# DB10012_ControlEtherCAT.net
KiCad netlist of a schematic drawn in Altium Designer
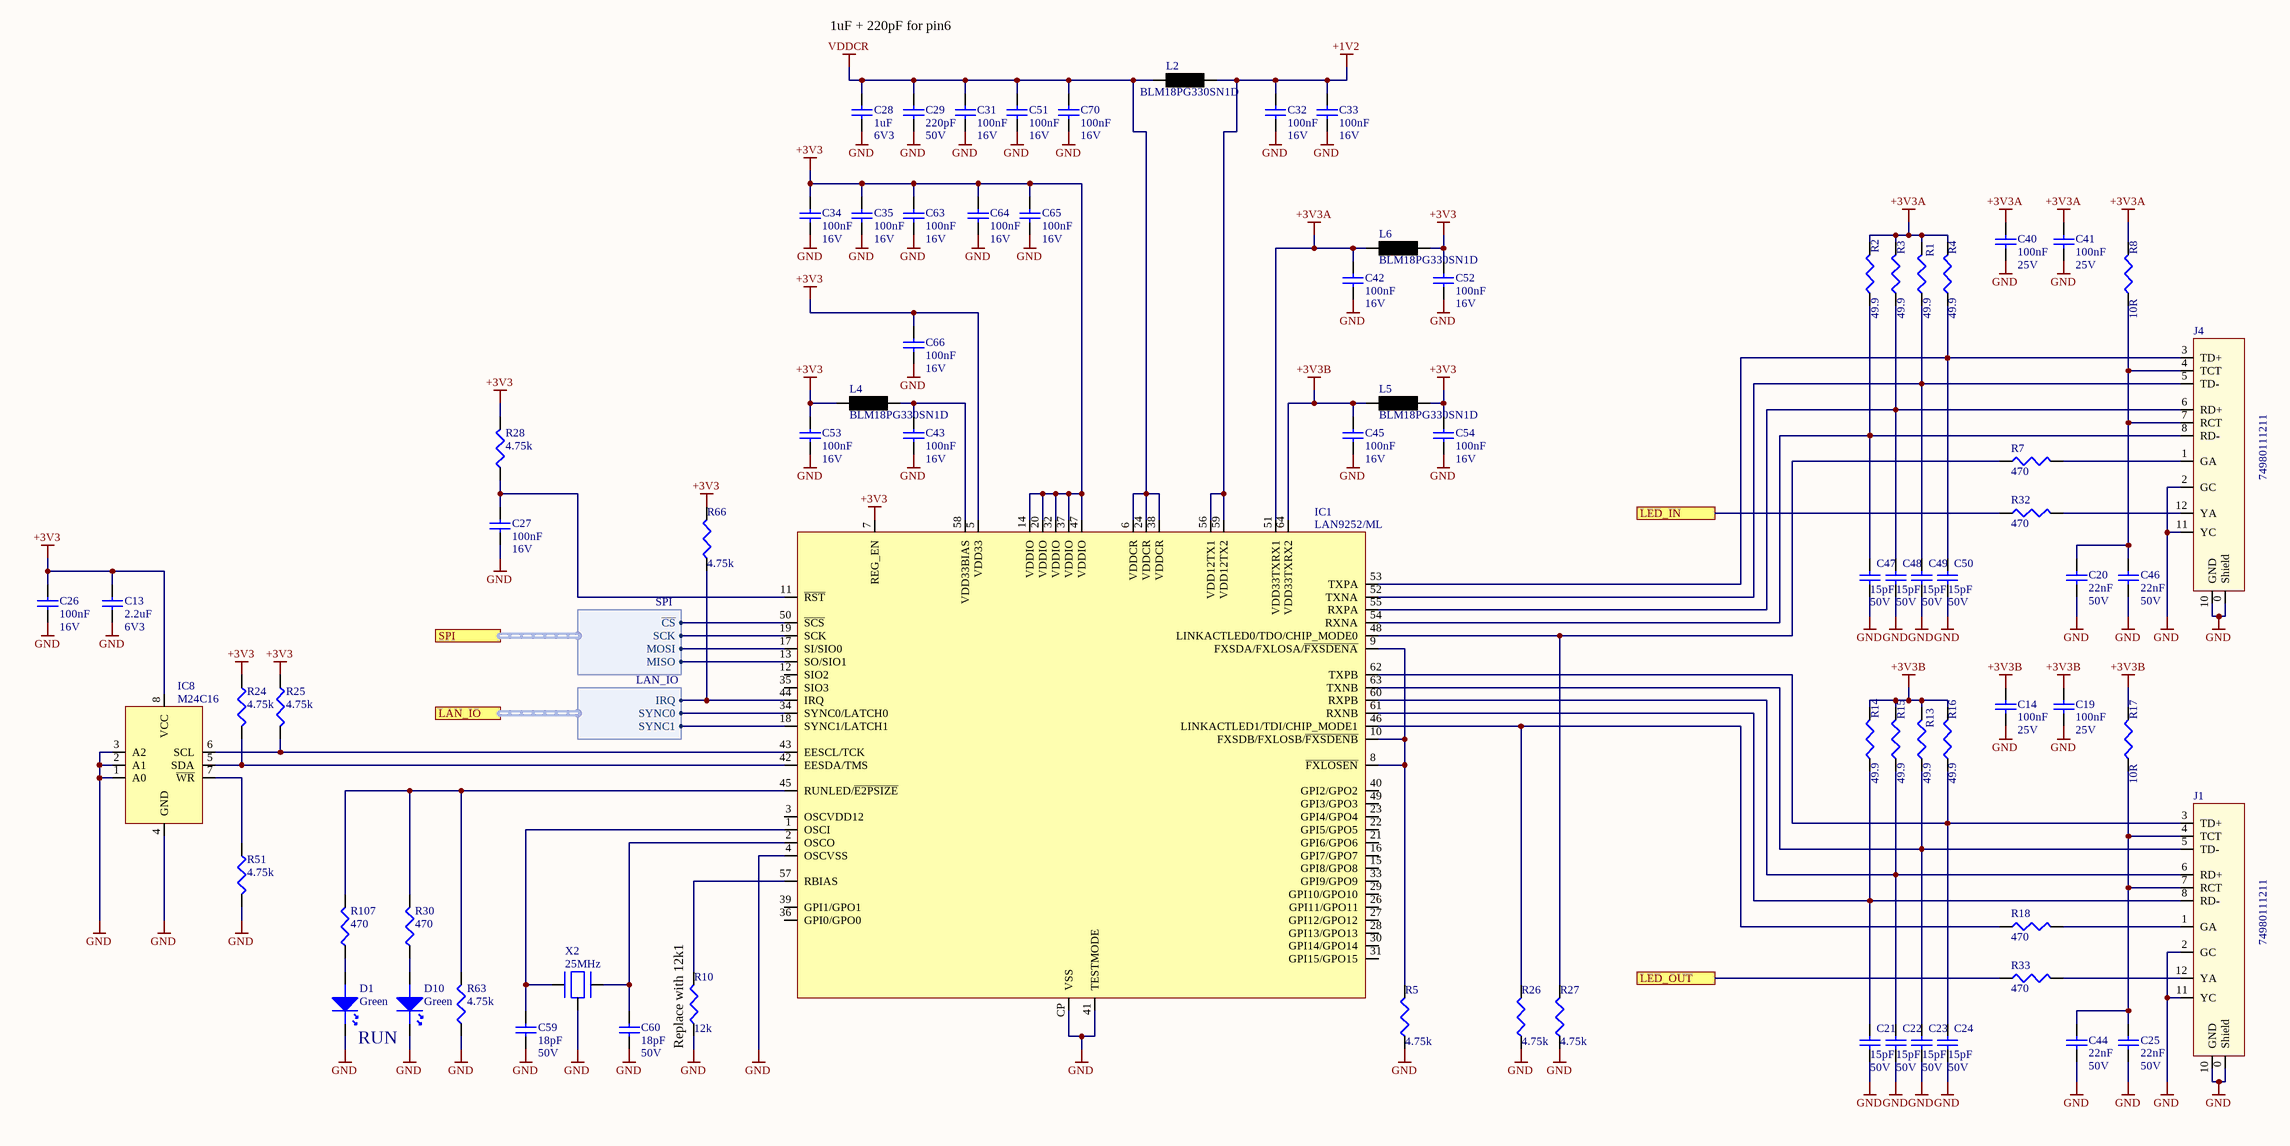
[diagram p0: DB10012_ControlEtherCAT.SchDoc]

(export (version "E")
  (design (tool "Eeschema 10.0.6"))
  (components
    (comp (ref "C13")
      (value "2.2uF")
      (footprint "C0402")
      (description "Capacitor, 2.2uF, 6.3V, X5R")
      (fields (field (name "VOLTAGE RATING") "6V3"))
      (libsource (lib "AR_Capacitors_Ceramic") (part "2.2uF/0402/CER/6.3V"))
    )
    (comp (ref "C14")
      (value "100nF")
      (footprint "C0402")
      (description "Capacitor, 100nF, 25V, X7R")
      (fields (field (name "VOLTAGE RATING") "25V"))
      (libsource (lib "AR_Capacitors_Ceramic") (part "100nF/0402/CER/25V"))
    )
    (comp (ref "C19")
      (value "100nF")
      (footprint "C0402")
      (description "Capacitor, 100nF, 25V, X7R")
      (fields (field (name "VOLTAGE RATING") "25V"))
      (libsource (lib "AR_Capacitors_Ceramic") (part "100nF/0402/CER/25V"))
    )
    (comp (ref "C20")
      (value "22nF")
      (footprint "C0402")
      (description "Capacitor, 22nF, 50V, X7R")
      (fields (field (name "VOLTAGE RATING") "50V"))
      (libsource (lib "AR_Capacitors_Ceramic") (part "22nF/0402/CER/50V"))
    )
    (comp (ref "C21")
      (value "15pF")
      (footprint "C0402")
      (description "Capacitor, 15pF, 50V, C0G")
      (fields (field (name "VOLTAGE RATING") "50V"))
      (libsource (lib "AR_Capacitors_Ceramic") (part "15pF/0402/CER/50V"))
    )
    (comp (ref "C22")
      (value "15pF")
      (footprint "C0402")
      (description "Capacitor, 15pF, 50V, C0G")
      (fields (field (name "VOLTAGE RATING") "50V"))
      (libsource (lib "AR_Capacitors_Ceramic") (part "15pF/0402/CER/50V"))
    )
    (comp (ref "C23")
      (value "15pF")
      (footprint "C0402")
      (description "Capacitor, 15pF, 50V, C0G")
      (fields (field (name "VOLTAGE RATING") "50V"))
      (libsource (lib "AR_Capacitors_Ceramic") (part "15pF/0402/CER/50V"))
    )
    (comp (ref "C24")
      (value "15pF")
      (footprint "C0402")
      (description "Capacitor, 15pF, 50V, C0G")
      (fields (field (name "VOLTAGE RATING") "50V"))
      (libsource (lib "AR_Capacitors_Ceramic") (part "15pF/0402/CER/50V"))
    )
    (comp (ref "C25")
      (value "22nF")
      (footprint "C0402")
      (description "Capacitor, 22nF, 50V, X7R")
      (fields (field (name "VOLTAGE RATING") "50V"))
      (libsource (lib "AR_Capacitors_Ceramic") (part "22nF/0402/CER/50V"))
    )
    (comp (ref "C26")
      (value "100nF")
      (footprint "C0402")
      (description "Capacitor, 100nF, 16V, X7R")
      (fields (field (name "VOLTAGE RATING") "16V"))
      (libsource (lib "AR_Capacitors_Ceramic") (part "100nF/0402/CER/16V"))
    )
    (comp (ref "C27")
      (value "100nF")
      (footprint "C0402")
      (description "Capacitor, 100nF, 16V, X7R")
      (fields (field (name "VOLTAGE RATING") "16V"))
      (libsource (lib "AR_Capacitors_Ceramic") (part "100nF/0402/CER/16V"))
    )
    (comp (ref "C28")
      (value "1uF")
      (footprint "C0402")
      (description "Capacitor, 1uF, 6.3V, X5R")
      (fields (field (name "VOLTAGE RATING") "6V3"))
      (libsource (lib "AR_Capacitors_Ceramic") (part "1uF/0402/CER/6.3V"))
    )
    (comp (ref "C29")
      (value "220pF")
      (footprint "C0402")
      (description "Capacitor, 220pF, 50V, NP0")
      (fields (field (name "VOLTAGE RATING") "50V"))
      (libsource (lib "AR_Capacitors_Ceramic") (part "220pF/0402/CER/50V"))
    )
    (comp (ref "C31")
      (value "100nF")
      (footprint "C0402")
      (description "Capacitor, 100nF, 16V, X7R")
      (fields (field (name "VOLTAGE RATING") "16V"))
      (libsource (lib "AR_Capacitors_Ceramic") (part "100nF/0402/CER/16V"))
    )
    (comp (ref "C32")
      (value "100nF")
      (footprint "C0402")
      (description "Capacitor, 100nF, 16V, X7R")
      (fields (field (name "VOLTAGE RATING") "16V"))
      (libsource (lib "AR_Capacitors_Ceramic") (part "100nF/0402/CER/16V"))
    )
    (comp (ref "C33")
      (value "100nF")
      (footprint "C0402")
      (description "Capacitor, 100nF, 16V, X7R")
      (fields (field (name "VOLTAGE RATING") "16V"))
      (libsource (lib "AR_Capacitors_Ceramic") (part "100nF/0402/CER/16V"))
    )
    (comp (ref "C34")
      (value "100nF")
      (footprint "C0402")
      (description "Capacitor, 100nF, 16V, X7R")
      (fields (field (name "VOLTAGE RATING") "16V"))
      (libsource (lib "AR_Capacitors_Ceramic") (part "100nF/0402/CER/16V"))
    )
    (comp (ref "C35")
      (value "100nF")
      (footprint "C0402")
      (description "Capacitor, 100nF, 16V, X7R")
      (fields (field (name "VOLTAGE RATING") "16V"))
      (libsource (lib "AR_Capacitors_Ceramic") (part "100nF/0402/CER/16V"))
    )
    (comp (ref "C40")
      (value "100nF")
      (footprint "C0402")
      (description "Capacitor, 100nF, 25V, X7R")
      (fields (field (name "VOLTAGE RATING") "25V"))
      (libsource (lib "AR_Capacitors_Ceramic") (part "100nF/0402/CER/25V"))
    )
    (comp (ref "C41")
      (value "100nF")
      (footprint "C0402")
      (description "Capacitor, 100nF, 25V, X7R")
      (fields (field (name "VOLTAGE RATING") "25V"))
      (libsource (lib "AR_Capacitors_Ceramic") (part "100nF/0402/CER/25V"))
    )
    (comp (ref "C42")
      (value "100nF")
      (footprint "C0402")
      (description "Capacitor, 100nF, 16V, X7R")
      (fields (field (name "VOLTAGE RATING") "16V"))
      (libsource (lib "AR_Capacitors_Ceramic") (part "100nF/0402/CER/16V"))
    )
    (comp (ref "C43")
      (value "100nF")
      (footprint "C0402")
      (description "Capacitor, 100nF, 16V, X7R")
      (fields (field (name "VOLTAGE RATING") "16V"))
      (libsource (lib "AR_Capacitors_Ceramic") (part "100nF/0402/CER/16V"))
    )
    (comp (ref "C44")
      (value "22nF")
      (footprint "C0402")
      (description "Capacitor, 22nF, 50V, X7R")
      (fields (field (name "VOLTAGE RATING") "50V"))
      (libsource (lib "AR_Capacitors_Ceramic") (part "22nF/0402/CER/50V"))
    )
    (comp (ref "C45")
      (value "100nF")
      (footprint "C0402")
      (description "Capacitor, 100nF, 16V, X7R")
      (fields (field (name "VOLTAGE RATING") "16V"))
      (libsource (lib "AR_Capacitors_Ceramic") (part "100nF/0402/CER/16V"))
    )
    (comp (ref "C46")
      (value "22nF")
      (footprint "C0402")
      (description "Capacitor, 22nF, 50V, X7R")
      (fields (field (name "VOLTAGE RATING") "50V"))
      (libsource (lib "AR_Capacitors_Ceramic") (part "22nF/0402/CER/50V"))
    )
    (comp (ref "C47")
      (value "15pF")
      (footprint "C0402")
      (description "Capacitor, 15pF, 50V, C0G")
      (fields (field (name "VOLTAGE RATING") "50V"))
      (libsource (lib "AR_Capacitors_Ceramic") (part "15pF/0402/CER/50V"))
    )
    (comp (ref "C48")
      (value "15pF")
      (footprint "C0402")
      (description "Capacitor, 15pF, 50V, C0G")
      (fields (field (name "VOLTAGE RATING") "50V"))
      (libsource (lib "AR_Capacitors_Ceramic") (part "15pF/0402/CER/50V"))
    )
    (comp (ref "C49")
      (value "15pF")
      (footprint "C0402")
      (description "Capacitor, 15pF, 50V, C0G")
      (fields (field (name "VOLTAGE RATING") "50V"))
      (libsource (lib "AR_Capacitors_Ceramic") (part "15pF/0402/CER/50V"))
    )
    (comp (ref "C50")
      (value "15pF")
      (footprint "C0402")
      (description "Capacitor, 15pF, 50V, C0G")
      (fields (field (name "VOLTAGE RATING") "50V"))
      (libsource (lib "AR_Capacitors_Ceramic") (part "15pF/0402/CER/50V"))
    )
    (comp (ref "C51")
      (value "100nF")
      (footprint "C0402")
      (description "Capacitor, 100nF, 16V, X7R")
      (fields (field (name "VOLTAGE RATING") "16V"))
      (libsource (lib "AR_Capacitors_Ceramic") (part "100nF/0402/CER/16V"))
    )
    (comp (ref "C52")
      (value "100nF")
      (footprint "C0402")
      (description "Capacitor, 100nF, 16V, X7R")
      (fields (field (name "VOLTAGE RATING") "16V"))
      (libsource (lib "AR_Capacitors_Ceramic") (part "100nF/0402/CER/16V"))
    )
    (comp (ref "C53")
      (value "100nF")
      (footprint "C0402")
      (description "Capacitor, 100nF, 16V, X7R")
      (fields (field (name "VOLTAGE RATING") "16V"))
      (libsource (lib "AR_Capacitors_Ceramic") (part "100nF/0402/CER/16V"))
    )
    (comp (ref "C54")
      (value "100nF")
      (footprint "C0402")
      (description "Capacitor, 100nF, 16V, X7R")
      (fields (field (name "VOLTAGE RATING") "16V"))
      (libsource (lib "AR_Capacitors_Ceramic") (part "100nF/0402/CER/16V"))
    )
    (comp (ref "C59")
      (value "18pF")
      (footprint "C0402")
      (description "Capacitor, 18pF, 50V, NP0")
      (fields (field (name "VOLTAGE RATING") "50V"))
      (libsource (lib "AR_Capacitors_Ceramic") (part "18pF/0402/CER/50V"))
    )
    (comp (ref "C60")
      (value "18pF")
      (footprint "C0402")
      (description "Capacitor, 18pF, 50V, NP0")
      (fields (field (name "VOLTAGE RATING") "50V"))
      (libsource (lib "AR_Capacitors_Ceramic") (part "18pF/0402/CER/50V"))
    )
    (comp (ref "C63")
      (value "100nF")
      (footprint "C0402")
      (description "Capacitor, 100nF, 16V, X7R")
      (fields (field (name "VOLTAGE RATING") "16V"))
      (libsource (lib "AR_Capacitors_Ceramic") (part "100nF/0402/CER/16V"))
    )
    (comp (ref "C64")
      (value "100nF")
      (footprint "C0402")
      (description "Capacitor, 100nF, 16V, X7R")
      (fields (field (name "VOLTAGE RATING") "16V"))
      (libsource (lib "AR_Capacitors_Ceramic") (part "100nF/0402/CER/16V"))
    )
    (comp (ref "C65")
      (value "100nF")
      (footprint "C0402")
      (description "Capacitor, 100nF, 16V, X7R")
      (fields (field (name "VOLTAGE RATING") "16V"))
      (libsource (lib "AR_Capacitors_Ceramic") (part "100nF/0402/CER/16V"))
    )
    (comp (ref "C66")
      (value "100nF")
      (footprint "C0402")
      (description "Capacitor, 100nF, 16V, X7R")
      (fields (field (name "VOLTAGE RATING") "16V"))
      (libsource (lib "AR_Capacitors_Ceramic") (part "100nF/0402/CER/16V"))
    )
    (comp (ref "C70")
      (value "100nF")
      (footprint "C0402")
      (description "Capacitor, 100nF, 16V, X7R")
      (fields (field (name "VOLTAGE RATING") "16V"))
      (libsource (lib "AR_Capacitors_Ceramic") (part "100nF/0402/CER/16V"))
    )
    (comp (ref "D1")
      (value "Green")
      (footprint "D-0805")
      (description "Led, Green, Li:12mcd, Vf:2.2V, If:0.02A")
      (libsource (lib "AR_Misc") (part "KP-2012SGC"))
    )
    (comp (ref "D10")
      (value "Green")
      (footprint "D-0805")
      (description "Led, Green, Li:12mcd, Vf:2.2V, If:0.02A")
      (libsource (lib "AR_Misc") (part "KP-2012SGC"))
    )
    (comp (ref "IC1")
      (value "LAN9252/ML")
      (footprint "QFN64_Rect")
      (description "EtherCAT Slave Controller")
      (libsource (lib "AR_ICs") (part "LAN9252/ML"))
    )
    (comp (ref "IC8")
      (value "M24C16")
      (footprint "SO-8")
      (description "SERIAL EEPROM, 16KBIT, 400KHZ")
      (libsource (lib "AR_ICs") (part "M24C16-WMN6P"))
    )
    (comp (ref "J1")
      (value "74980111211")
      (footprint "74980111211")
      (description "RJ45 With LAN TRANSFRMR")
      (libsource (lib "AR_Connectors") (part "74980111211"))
    )
    (comp (ref "J4")
      (value "74980111211")
      (footprint "74980111211")
      (description "RJ45 With LAN TRANSFRMR")
      (libsource (lib "AR_Connectors") (part "74980111211"))
    )
    (comp (ref "L2")
      (value "BLM18PG330SN1D")
      (footprint "L0603")
      (description "Ferrite Bead, Impedance:33ohm, DC Resistance Max:0.025ohm, DC Current Rating:3A")
      (libsource (lib "AR_Inductors") (part "BLM18PG330SN1D"))
    )
    (comp (ref "L4")
      (value "BLM18PG330SN1D")
      (footprint "L0603")
      (description "Ferrite Bead, Impedance:33ohm, DC Resistance Max:0.025ohm, DC Current Rating:3A")
      (libsource (lib "") (part "BLM18PG330SN1D_1"))
    )
    (comp (ref "L5")
      (value "BLM18PG330SN1D")
      (footprint "L0603")
      (description "Ferrite Bead, Impedance:33ohm, DC Resistance Max:0.025ohm, DC Current Rating:3A")
      (libsource (lib "AR_Inductors") (part "BLM18PG330SN1D"))
    )
    (comp (ref "L6")
      (value "BLM18PG330SN1D")
      (footprint "L0603")
      (description "Ferrite Bead, Impedance:33ohm, DC Resistance Max:0.025ohm, DC Current Rating:3A")
      (libsource (lib "AR_Inductors") (part "BLM18PG330SN1D"))
    )
    (comp (ref "R1")
      (value "49.9")
      (footprint "0402")
      (description "Resistor, 49.9, 0.1%, 0.0625W, 50V, 100PPM, 0402")
      (libsource (lib "AR_Resistors_SMD") (part "49.9/0402/0063W/50V"))
    )
    (comp (ref "R2")
      (value "49.9")
      (footprint "0402")
      (description "Resistor, 49.9, 0.1%, 0.0625W, 50V, 100PPM, 0402")
      (libsource (lib "AR_Resistors_SMD") (part "49.9/0402/0063W/50V"))
    )
    (comp (ref "R3")
      (value "49.9")
      (footprint "0402")
      (description "Resistor, 49.9, 0.1%, 0.0625W, 50V, 100PPM, 0402")
      (libsource (lib "AR_Resistors_SMD") (part "49.9/0402/0063W/50V"))
    )
    (comp (ref "R4")
      (value "49.9")
      (footprint "0402")
      (description "Resistor, 49.9, 0.1%, 0.0625W, 50V, 100PPM, 0402")
      (libsource (lib "AR_Resistors_SMD") (part "49.9/0402/0063W/50V"))
    )
    (comp (ref "R5")
      (value "4.75k")
      (footprint "0402")
      (description "Resistor, 4.75k, 0.1%, 0.0625W, 50V, 100PPM, 0402")
      (libsource (lib "AR_Resistors_SMD") (part "4.75k/0402/0063W/50V"))
    )
    (comp (ref "R7")
      (value "470")
      (footprint "0402")
      (description "Resistor, 470, 1%, 0.0625W, 50V, 100PPM, 0402")
      (libsource (lib "AR_Resistors_SMD") (part "470/0402/0063W/50V"))
    )
    (comp (ref "R8")
      (value "10R")
      (footprint "0603")
      (description "Resistor, 10R, 1%, 0.125W, 50V, 200PPM, 0603")
      (libsource (lib "AR_Resistors_SMD") (part "10/0603/0125W/50V"))
    )
    (comp (ref "R10")
      (value "12k")
      (footprint "0402")
      (description "Resistor, 12k, 1%, 0.0625W, 50V, 100PPM, 0402")
      (libsource (lib "AR_Resistors_SMD") (part "12k/0402/0063W/50V"))
    )
    (comp (ref "R13")
      (value "49.9")
      (footprint "0402")
      (description "Resistor, 49.9, 0.1%, 0.0625W, 50V, 100PPM, 0402")
      (libsource (lib "AR_Resistors_SMD") (part "49.9/0402/0063W/50V"))
    )
    (comp (ref "R14")
      (value "49.9")
      (footprint "0402")
      (description "Resistor, 49.9, 0.1%, 0.0625W, 50V, 100PPM, 0402")
      (libsource (lib "AR_Resistors_SMD") (part "49.9/0402/0063W/50V"))
    )
    (comp (ref "R15")
      (value "49.9")
      (footprint "0402")
      (description "Resistor, 49.9, 0.1%, 0.0625W, 50V, 100PPM, 0402")
      (libsource (lib "AR_Resistors_SMD") (part "49.9/0402/0063W/50V"))
    )
    (comp (ref "R16")
      (value "49.9")
      (footprint "0402")
      (description "Resistor, 49.9, 0.1%, 0.0625W, 50V, 100PPM, 0402")
      (libsource (lib "AR_Resistors_SMD") (part "49.9/0402/0063W/50V"))
    )
    (comp (ref "R17")
      (value "10R")
      (footprint "0603")
      (description "Resistor, 10R, 1%, 0.125W, 50V, 200PPM, 0603")
      (libsource (lib "AR_Resistors_SMD") (part "10/0603/0125W/50V"))
    )
    (comp (ref "R18")
      (value "470")
      (footprint "0402")
      (description "Resistor, 470, 1%, 0.0625W, 50V, 100PPM, 0402")
      (libsource (lib "AR_Resistors_SMD") (part "470/0402/0063W/50V"))
    )
    (comp (ref "R24")
      (value "4.75k")
      (footprint "0402")
      (description "Resistor, 4.75k, 0.1%, 0.0625W, 50V, 100PPM, 0402")
      (libsource (lib "AR_Resistors_SMD") (part "4.75k/0402/0063W/50V"))
    )
    (comp (ref "R25")
      (value "4.75k")
      (footprint "0402")
      (description "Resistor, 4.75k, 0.1%, 0.0625W, 50V, 100PPM, 0402")
      (libsource (lib "AR_Resistors_SMD") (part "4.75k/0402/0063W/50V"))
    )
    (comp (ref "R26")
      (value "4.75k")
      (footprint "0402")
      (description "Resistor, 4.75k, 0.1%, 0.0625W, 50V, 100PPM, 0402")
      (libsource (lib "AR_Resistors_SMD") (part "4.75k/0402/0063W/50V"))
    )
    (comp (ref "R27")
      (value "4.75k")
      (footprint "0402")
      (description "Resistor, 4.75k, 0.1%, 0.0625W, 50V, 100PPM, 0402")
      (libsource (lib "AR_Resistors_SMD") (part "4.75k/0402/0063W/50V"))
    )
    (comp (ref "R28")
      (value "4.75k")
      (footprint "0402")
      (description "Resistor, 4.75k, 0.1%, 0.0625W, 50V, 100PPM, 0402")
      (libsource (lib "AR_Resistors_SMD") (part "4.75k/0402/0063W/50V"))
    )
    (comp (ref "R30")
      (value "470")
      (footprint "0402")
      (description "Resistor, 470, 1%, 0.0625W, 50V, 100PPM, 0402")
      (libsource (lib "AR_Resistors_SMD") (part "470/0402/0063W/50V"))
    )
    (comp (ref "R32")
      (value "470")
      (footprint "0402")
      (description "Resistor, 470, 1%, 0.0625W, 50V, 100PPM, 0402")
      (libsource (lib "AR_Resistors_SMD") (part "470/0402/0063W/50V"))
    )
    (comp (ref "R33")
      (value "470")
      (footprint "0402")
      (description "Resistor, 470, 1%, 0.0625W, 50V, 100PPM, 0402")
      (libsource (lib "AR_Resistors_SMD") (part "470/0402/0063W/50V"))
    )
    (comp (ref "R51")
      (value "4.75k")
      (footprint "0402")
      (description "Resistor, 4.75k, 0.1%, 0.0625W, 50V, 100PPM, 0402")
      (libsource (lib "AR_Resistors_SMD") (part "4.75k/0402/0063W/50V"))
    )
    (comp (ref "R63")
      (value "4.75k")
      (footprint "0402")
      (description "Resistor, 4.75k, 0.1%, 0.0625W, 50V, 100PPM, 0402")
      (libsource (lib "AR_Resistors_SMD") (part "4.75k/0402/0063W/50V"))
    )
    (comp (ref "R66")
      (value "4.75k")
      (footprint "0402")
      (description "Resistor, 4.75k, 0.1%, 0.0625W, 50V, 100PPM, 0402")
      (libsource (lib "AR_Resistors_SMD") (part "4.75k/0402/0063W/50V"))
    )
    (comp (ref "R107")
      (value "470")
      (footprint "0402")
      (description "Resistor, 470, 1%, 0.0625W, 50V, 100PPM, 0402")
      (libsource (lib "AR_Resistors_SMD") (part "470/0402/0063W/50V"))
    )
    (comp (ref "X2")
      (value "25MHz")
      (footprint "7M")
      (description "CRYSTAL, 25MHz,18PF CL, 3.2X2.5MM SMT")
      (libsource (lib "AR_Crystals") (part "7M-25.000MAAJ-T"))
    )
  )
  (nets
    (net (code "3") (name "+1V2") (class "Default")
      (node (ref "C32") (pin "2") (pinfunction "2_2") (pintype "passive"))
      (node (ref "C33") (pin "2") (pinfunction "2_2") (pintype "passive"))
      (node (ref "IC1") (pin "56") (pinfunction "VDD12TX1_56") (pintype "passive"))
      (node (ref "IC1") (pin "59") (pinfunction "VDD12TX2_59") (pintype "passive"))
      (node (ref "L2") (pin "2") (pinfunction "2_2") (pintype "passive"))
    )
    (net (code "4") (name "+3V3") (class "Default")
      (node (ref "C13") (pin "2") (pinfunction "2_2") (pintype "passive"))
      (node (ref "C26") (pin "2") (pinfunction "2_2") (pintype "passive"))
      (node (ref "C34") (pin "2") (pinfunction "2_2") (pintype "passive"))
      (node (ref "C35") (pin "2") (pinfunction "2_2") (pintype "passive"))
      (node (ref "C52") (pin "2") (pinfunction "2_2") (pintype "passive"))
      (node (ref "C53") (pin "2") (pinfunction "2_2") (pintype "passive"))
      (node (ref "C54") (pin "2") (pinfunction "2_2") (pintype "passive"))
      (node (ref "C63") (pin "2") (pinfunction "2_2") (pintype "passive"))
      (node (ref "C64") (pin "2") (pinfunction "2_2") (pintype "passive"))
      (node (ref "C65") (pin "2") (pinfunction "2_2") (pintype "passive"))
      (node (ref "C66") (pin "2") (pinfunction "2_2") (pintype "passive"))
      (node (ref "IC1") (pin "14") (pinfunction "VDDIO_14") (pintype "passive"))
      (node (ref "IC1") (pin "20") (pinfunction "VDDIO_20") (pintype "passive"))
      (node (ref "IC1") (pin "32") (pinfunction "VDDIO_32") (pintype "passive"))
      (node (ref "IC1") (pin "37") (pinfunction "VDDIO_37") (pintype "passive"))
      (node (ref "IC1") (pin "47") (pinfunction "VDDIO_47") (pintype "passive"))
      (node (ref "IC1") (pin "5") (pinfunction "VDD33_5") (pintype "passive"))
      (node (ref "IC1") (pin "7") (pinfunction "REG_EN_7") (pintype "passive"))
      (node (ref "IC8") (pin "8") (pinfunction "VCC_8") (pintype "passive"))
      (node (ref "L4") (pin "2") (pinfunction "2_2") (pintype "passive"))
      (node (ref "L5") (pin "2") (pinfunction "2_2") (pintype "passive"))
      (node (ref "L6") (pin "2") (pinfunction "2_2") (pintype "passive"))
      (node (ref "R24") (pin "2") (pinfunction "2_2") (pintype "passive"))
      (node (ref "R25") (pin "2") (pinfunction "2_2") (pintype "passive"))
      (node (ref "R28") (pin "2") (pinfunction "2_2") (pintype "passive"))
      (node (ref "R66") (pin "2") (pinfunction "2_2") (pintype "passive"))
    )
    (net (code "5") (name "+3V3A") (class "Default")
      (node (ref "C40") (pin "2") (pinfunction "2_2") (pintype "passive"))
      (node (ref "C41") (pin "2") (pinfunction "2_2") (pintype "passive"))
      (node (ref "C42") (pin "2") (pinfunction "2_2") (pintype "passive"))
      (node (ref "IC1") (pin "51") (pinfunction "VDD33TXRX1_51") (pintype "passive"))
      (node (ref "L6") (pin "1") (pinfunction "1_1") (pintype "passive"))
      (node (ref "R1") (pin "2") (pinfunction "2_2") (pintype "passive"))
      (node (ref "R2") (pin "2") (pinfunction "2_2") (pintype "passive"))
      (node (ref "R3") (pin "2") (pinfunction "2_2") (pintype "passive"))
      (node (ref "R4") (pin "2") (pinfunction "2_2") (pintype "passive"))
      (node (ref "R8") (pin "2") (pinfunction "2_2") (pintype "passive"))
    )
    (net (code "6") (name "+3V3B") (class "Default")
      (node (ref "C14") (pin "2") (pinfunction "2_2") (pintype "passive"))
      (node (ref "C19") (pin "2") (pinfunction "2_2") (pintype "passive"))
      (node (ref "C45") (pin "2") (pinfunction "2_2") (pintype "passive"))
      (node (ref "IC1") (pin "64") (pinfunction "VDD33TXRX2_64") (pintype "passive"))
      (node (ref "L5") (pin "1") (pinfunction "1_1") (pintype "passive"))
      (node (ref "R13") (pin "2") (pinfunction "2_2") (pintype "passive"))
      (node (ref "R14") (pin "2") (pinfunction "2_2") (pintype "passive"))
      (node (ref "R15") (pin "2") (pinfunction "2_2") (pintype "passive"))
      (node (ref "R16") (pin "2") (pinfunction "2_2") (pintype "passive"))
      (node (ref "R17") (pin "2") (pinfunction "2_2") (pintype "passive"))
    )
    (net (code "7") (name "/IRQ") (class "Default")
      (node (ref "IC1") (pin "44") (pinfunction "IRQ_44") (pintype "passive"))
      (node (ref "R66") (pin "1") (pinfunction "1_1") (pintype "passive"))
    )
    (net (code "8") (name "/LED_IN") (class "Default")
      (node (ref "R32") (pin "1") (pinfunction "1_1") (pintype "passive"))
    )
    (net (code "9") (name "/LED_OUT") (class "Default")
      (node (ref "R33") (pin "1") (pinfunction "1_1") (pintype "passive"))
    )
    (net (code "10") (name "/MISO") (class "Default")
      (node (ref "IC1") (pin "13") (pinfunction "SO/SIO1_13") (pintype "passive"))
    )
    (net (code "11") (name "/MOSI") (class "Default")
      (node (ref "IC1") (pin "17") (pinfunction "SI/SIO0_17") (pintype "passive"))
    )
    (net (code "12") (name "/SCK") (class "Default")
      (node (ref "IC1") (pin "19") (pinfunction "SCK_19") (pintype "passive"))
    )
    (net (code "13") (name "/SYNC0") (class "Default")
      (node (ref "IC1") (pin "34") (pinfunction "SYNC0/LATCH0_34") (pintype "passive"))
    )
    (net (code "14") (name "/SYNC1") (class "Default")
      (node (ref "IC1") (pin "18") (pinfunction "SYNC1/LATCH1_18") (pintype "passive"))
    )
    (net (code "17") (name "/~{CS}") (class "Default")
      (node (ref "IC1") (pin "50") (pinfunction "~{SCS}_50") (pintype "passive"))
    )
    (net (code "18") (name "GND") (class "Default")
      (node (ref "C13") (pin "1") (pinfunction "1_1") (pintype "passive"))
      (node (ref "C14") (pin "1") (pinfunction "1_1") (pintype "passive"))
      (node (ref "C19") (pin "1") (pinfunction "1_1") (pintype "passive"))
      (node (ref "C20") (pin "1") (pinfunction "1_1") (pintype "passive"))
      (node (ref "C21") (pin "1") (pinfunction "1_1") (pintype "passive"))
      (node (ref "C22") (pin "1") (pinfunction "1_1") (pintype "passive"))
      (node (ref "C23") (pin "1") (pinfunction "1_1") (pintype "passive"))
      (node (ref "C24") (pin "1") (pinfunction "1_1") (pintype "passive"))
      (node (ref "C25") (pin "1") (pinfunction "1_1") (pintype "passive"))
      (node (ref "C26") (pin "1") (pinfunction "1_1") (pintype "passive"))
      (node (ref "C27") (pin "1") (pinfunction "1_1") (pintype "passive"))
      (node (ref "C28") (pin "1") (pinfunction "1_1") (pintype "passive"))
      (node (ref "C29") (pin "1") (pinfunction "1_1") (pintype "passive"))
      (node (ref "C31") (pin "1") (pinfunction "1_1") (pintype "passive"))
      (node (ref "C32") (pin "1") (pinfunction "1_1") (pintype "passive"))
      (node (ref "C33") (pin "1") (pinfunction "1_1") (pintype "passive"))
      (node (ref "C34") (pin "1") (pinfunction "1_1") (pintype "passive"))
      (node (ref "C35") (pin "1") (pinfunction "1_1") (pintype "passive"))
      (node (ref "C40") (pin "1") (pinfunction "1_1") (pintype "passive"))
      (node (ref "C41") (pin "1") (pinfunction "1_1") (pintype "passive"))
      (node (ref "C42") (pin "1") (pinfunction "1_1") (pintype "passive"))
      (node (ref "C43") (pin "1") (pinfunction "1_1") (pintype "passive"))
      (node (ref "C44") (pin "1") (pinfunction "1_1") (pintype "passive"))
      (node (ref "C45") (pin "1") (pinfunction "1_1") (pintype "passive"))
      (node (ref "C46") (pin "1") (pinfunction "1_1") (pintype "passive"))
      (node (ref "C47") (pin "1") (pinfunction "1_1") (pintype "passive"))
      (node (ref "C48") (pin "1") (pinfunction "1_1") (pintype "passive"))
      (node (ref "C49") (pin "1") (pinfunction "1_1") (pintype "passive"))
      (node (ref "C50") (pin "1") (pinfunction "1_1") (pintype "passive"))
      (node (ref "C51") (pin "1") (pinfunction "1_1") (pintype "passive"))
      (node (ref "C52") (pin "1") (pinfunction "1_1") (pintype "passive"))
      (node (ref "C53") (pin "1") (pinfunction "1_1") (pintype "passive"))
      (node (ref "C54") (pin "1") (pinfunction "1_1") (pintype "passive"))
      (node (ref "C59") (pin "1") (pinfunction "1_1") (pintype "passive"))
      (node (ref "C60") (pin "1") (pinfunction "1_1") (pintype "passive"))
      (node (ref "C63") (pin "1") (pinfunction "1_1") (pintype "passive"))
      (node (ref "C64") (pin "1") (pinfunction "1_1") (pintype "passive"))
      (node (ref "C65") (pin "1") (pinfunction "1_1") (pintype "passive"))
      (node (ref "C66") (pin "1") (pinfunction "1_1") (pintype "passive"))
      (node (ref "C70") (pin "1") (pinfunction "1_1") (pintype "passive"))
      (node (ref "D1") (pin "K") (pinfunction "K_K") (pintype "passive"))
      (node (ref "D10") (pin "K") (pinfunction "K_K") (pintype "passive"))
      (node (ref "IC1") (pin "4") (pinfunction "OSCVSS_4") (pintype "passive"))
      (node (ref "IC1") (pin "41") (pinfunction "TESTMODE_41") (pintype "passive"))
      (node (ref "IC1") (pin "CP") (pinfunction "VSS_CP") (pintype "passive"))
      (node (ref "IC8") (pin "1") (pinfunction "A0_1") (pintype "passive"))
      (node (ref "IC8") (pin "2") (pinfunction "A1_2") (pintype "passive"))
      (node (ref "IC8") (pin "3") (pinfunction "A2_3") (pintype "passive"))
      (node (ref "IC8") (pin "4") (pinfunction "GND_4") (pintype "passive"))
      (node (ref "J1") (pin "0") (pinfunction "Shield_0") (pintype "passive"))
      (node (ref "J1") (pin "10") (pinfunction "GND_10") (pintype "passive"))
      (node (ref "J1") (pin "11") (pinfunction "YC_11") (pintype "passive"))
      (node (ref "J1") (pin "2") (pinfunction "GC_2") (pintype "passive"))
      (node (ref "J4") (pin "0") (pinfunction "Shield_0") (pintype "passive"))
      (node (ref "J4") (pin "10") (pinfunction "GND_10") (pintype "passive"))
      (node (ref "J4") (pin "11") (pinfunction "YC_11") (pintype "passive"))
      (node (ref "J4") (pin "2") (pinfunction "GC_2") (pintype "passive"))
      (node (ref "R10") (pin "1") (pinfunction "1_1") (pintype "passive"))
      (node (ref "R26") (pin "1") (pinfunction "1_1") (pintype "passive"))
      (node (ref "R27") (pin "1") (pinfunction "1_1") (pintype "passive"))
      (node (ref "R5") (pin "1") (pinfunction "1_1") (pintype "passive"))
      (node (ref "R51") (pin "1") (pinfunction "1_1") (pintype "passive"))
      (node (ref "R63") (pin "1") (pinfunction "1_1") (pintype "passive"))
      (node (ref "X2") (pin "0") (pinfunction "0_0") (pintype "power_in"))
    )
    (net (code "19") (name "Net-(D1-PadA)") (class "Default")
      (node (ref "D1") (pin "A") (pinfunction "A_A") (pintype "passive"))
      (node (ref "R107") (pin "1") (pinfunction "1_1") (pintype "passive"))
    )
    (net (code "20") (name "Net-(D10-PadA)") (class "Default")
      (node (ref "D10") (pin "A") (pinfunction "A_A") (pintype "passive"))
      (node (ref "R30") (pin "1") (pinfunction "1_1") (pintype "passive"))
    )
    (net (code "21") (name "Net-(IC1-EESCL{slash}TCK)") (class "Default")
      (node (ref "IC1") (pin "43") (pinfunction "EESCL/TCK_43") (pintype "passive"))
      (node (ref "IC8") (pin "6") (pinfunction "SCL_6") (pintype "passive"))
      (node (ref "R25") (pin "1") (pinfunction "1_1") (pintype "passive"))
    )
    (net (code "22") (name "Net-(IC1-EESDA{slash}TMS)") (class "Default")
      (node (ref "IC1") (pin "42") (pinfunction "EESDA/TMS_42") (pintype "passive"))
      (node (ref "IC8") (pin "5") (pinfunction "SDA_5") (pintype "passive"))
      (node (ref "R24") (pin "1") (pinfunction "1_1") (pintype "passive"))
    )
    (net (code "23") (name "Net-(IC1-FXSDA{slash}FXLOSA{slash}~{FXSDENA})") (class "Default")
      (node (ref "IC1") (pin "10") (pinfunction "FXSDB/FXLOSB/~{FXSDENB}_10") (pintype "passive"))
      (node (ref "IC1") (pin "8") (pinfunction "~{FXLOSEN}_8") (pintype "passive"))
      (node (ref "IC1") (pin "9") (pinfunction "FXSDA/FXLOSA/~{FXSDENA}_9") (pintype "passive"))
      (node (ref "R5") (pin "2") (pinfunction "2_2") (pintype "passive"))
    )
    (net (code "24") (name "Net-(IC1-LINKACTLED0{slash}TDO{slash}CHIP_MODE0)") (class "Default")
      (node (ref "IC1") (pin "48") (pinfunction "LINKACTLED0/TDO/CHIP_MODE0_48") (pintype "passive"))
      (node (ref "R27") (pin "2") (pinfunction "2_2") (pintype "passive"))
      (node (ref "R7") (pin "1") (pinfunction "1_1") (pintype "passive"))
    )
    (net (code "25") (name "Net-(IC1-LINKACTLED1{slash}TDI{slash}CHIP_MODE1)") (class "Default")
      (node (ref "IC1") (pin "46") (pinfunction "LINKACTLED1/TDI/CHIP_MODE1_46") (pintype "passive"))
      (node (ref "R18") (pin "1") (pinfunction "1_1") (pintype "passive"))
      (node (ref "R26") (pin "2") (pinfunction "2_2") (pintype "passive"))
    )
    (net (code "26") (name "Net-(IC1-OSCI)") (class "Default")
      (node (ref "C59") (pin "2") (pinfunction "2_2") (pintype "passive"))
      (node (ref "IC1") (pin "1") (pinfunction "OSCI_1") (pintype "passive"))
      (node (ref "X2") (pin "1") (pinfunction "1_1") (pintype "passive"))
    )
    (net (code "27") (name "Net-(IC1-OSCO)") (class "Default")
      (node (ref "C60") (pin "2") (pinfunction "2_2") (pintype "passive"))
      (node (ref "IC1") (pin "2") (pinfunction "OSCO_2") (pintype "passive"))
      (node (ref "X2") (pin "2") (pinfunction "2_2") (pintype "passive"))
    )
    (net (code "28") (name "Net-(IC1-RBIAS)") (class "Default")
      (node (ref "IC1") (pin "57") (pinfunction "RBIAS_57") (pintype "passive"))
      (node (ref "R10") (pin "2") (pinfunction "2_2") (pintype "passive"))
    )
    (net (code "29") (name "Net-(IC1-RUNLED{slash}~{E2PSIZE})") (class "Default")
      (node (ref "IC1") (pin "45") (pinfunction "RUNLED/~{E2PSIZE}_45") (pintype "passive"))
      (node (ref "R107") (pin "2") (pinfunction "2_2") (pintype "passive"))
      (node (ref "R30") (pin "2") (pinfunction "2_2") (pintype "passive"))
      (node (ref "R63") (pin "2") (pinfunction "2_2") (pintype "passive"))
    )
    (net (code "30") (name "Net-(IC1-RXNA)") (class "Default")
      (node (ref "C47") (pin "2") (pinfunction "2_2") (pintype "passive"))
      (node (ref "IC1") (pin "54") (pinfunction "RXNA_54") (pintype "passive"))
      (node (ref "J4") (pin "8") (pinfunction "RD-_8") (pintype "passive"))
      (node (ref "R2") (pin "1") (pinfunction "1_1") (pintype "passive"))
    )
    (net (code "31") (name "Net-(IC1-RXNB)") (class "Default")
      (node (ref "C21") (pin "2") (pinfunction "2_2") (pintype "passive"))
      (node (ref "IC1") (pin "61") (pinfunction "RXNB_61") (pintype "passive"))
      (node (ref "J1") (pin "8") (pinfunction "RD-_8") (pintype "passive"))
      (node (ref "R14") (pin "1") (pinfunction "1_1") (pintype "passive"))
    )
    (net (code "32") (name "Net-(IC1-RXPA)") (class "Default")
      (node (ref "C48") (pin "2") (pinfunction "2_2") (pintype "passive"))
      (node (ref "IC1") (pin "55") (pinfunction "RXPA_55") (pintype "passive"))
      (node (ref "J4") (pin "6") (pinfunction "RD+_6") (pintype "passive"))
      (node (ref "R3") (pin "1") (pinfunction "1_1") (pintype "passive"))
    )
    (net (code "33") (name "Net-(IC1-RXPB)") (class "Default")
      (node (ref "C22") (pin "2") (pinfunction "2_2") (pintype "passive"))
      (node (ref "IC1") (pin "60") (pinfunction "RXPB_60") (pintype "passive"))
      (node (ref "J1") (pin "6") (pinfunction "RD+_6") (pintype "passive"))
      (node (ref "R15") (pin "1") (pinfunction "1_1") (pintype "passive"))
    )
    (net (code "34") (name "Net-(IC1-TXNA)") (class "Default")
      (node (ref "C49") (pin "2") (pinfunction "2_2") (pintype "passive"))
      (node (ref "IC1") (pin "52") (pinfunction "TXNA_52") (pintype "passive"))
      (node (ref "J4") (pin "5") (pinfunction "TD-_5") (pintype "passive"))
      (node (ref "R1") (pin "1") (pinfunction "1_1") (pintype "passive"))
    )
    (net (code "35") (name "Net-(IC1-TXNB)") (class "Default")
      (node (ref "C23") (pin "2") (pinfunction "2_2") (pintype "passive"))
      (node (ref "IC1") (pin "63") (pinfunction "TXNB_63") (pintype "passive"))
      (node (ref "J1") (pin "5") (pinfunction "TD-_5") (pintype "passive"))
      (node (ref "R13") (pin "1") (pinfunction "1_1") (pintype "passive"))
    )
    (net (code "36") (name "Net-(IC1-TXPA)") (class "Default")
      (node (ref "C50") (pin "2") (pinfunction "2_2") (pintype "passive"))
      (node (ref "IC1") (pin "53") (pinfunction "TXPA_53") (pintype "passive"))
      (node (ref "J4") (pin "3") (pinfunction "TD+_3") (pintype "passive"))
      (node (ref "R4") (pin "1") (pinfunction "1_1") (pintype "passive"))
    )
    (net (code "37") (name "Net-(IC1-TXPB)") (class "Default")
      (node (ref "C24") (pin "2") (pinfunction "2_2") (pintype "passive"))
      (node (ref "IC1") (pin "62") (pinfunction "TXPB_62") (pintype "passive"))
      (node (ref "J1") (pin "3") (pinfunction "TD+_3") (pintype "passive"))
      (node (ref "R16") (pin "1") (pinfunction "1_1") (pintype "passive"))
    )
    (net (code "38") (name "Net-(IC1-VDD33BIAS)") (class "Default")
      (node (ref "C43") (pin "2") (pinfunction "2_2") (pintype "passive"))
      (node (ref "IC1") (pin "58") (pinfunction "VDD33BIAS_58") (pintype "passive"))
      (node (ref "L4") (pin "1") (pinfunction "1_1") (pintype "passive"))
    )
    (net (code "39") (name "Net-(IC1-~{RST})") (class "Default")
      (node (ref "C27") (pin "2") (pinfunction "2_2") (pintype "passive"))
      (node (ref "IC1") (pin "11") (pinfunction "~{RST}_11") (pintype "passive"))
      (node (ref "R28") (pin "1") (pinfunction "1_1") (pintype "passive"))
    )
    (net (code "40") (name "Net-(IC8-~{WR})") (class "Default")
      (node (ref "IC8") (pin "7") (pinfunction "~{WR}_7") (pintype "passive"))
      (node (ref "R51") (pin "2") (pinfunction "2_2") (pintype "passive"))
    )
    (net (code "41") (name "Net-(J1-GA)") (class "Default")
      (node (ref "J1") (pin "1") (pinfunction "GA_1") (pintype "passive"))
      (node (ref "R18") (pin "2") (pinfunction "2_2") (pintype "passive"))
    )
    (net (code "42") (name "Net-(J1-RCT)") (class "Default")
      (node (ref "C25") (pin "2") (pinfunction "2_2") (pintype "passive"))
      (node (ref "C44") (pin "2") (pinfunction "2_2") (pintype "passive"))
      (node (ref "J1") (pin "4") (pinfunction "TCT_4") (pintype "passive"))
      (node (ref "J1") (pin "7") (pinfunction "RCT_7") (pintype "passive"))
      (node (ref "R17") (pin "1") (pinfunction "1_1") (pintype "passive"))
    )
    (net (code "43") (name "Net-(J1-YA)") (class "Default")
      (node (ref "J1") (pin "12") (pinfunction "YA_12") (pintype "passive"))
      (node (ref "R33") (pin "2") (pinfunction "2_2") (pintype "passive"))
    )
    (net (code "44") (name "Net-(J4-GA)") (class "Default")
      (node (ref "J4") (pin "1") (pinfunction "GA_1") (pintype "passive"))
      (node (ref "R7") (pin "2") (pinfunction "2_2") (pintype "passive"))
    )
    (net (code "45") (name "Net-(J4-RCT)") (class "Default")
      (node (ref "C20") (pin "2") (pinfunction "2_2") (pintype "passive"))
      (node (ref "C46") (pin "2") (pinfunction "2_2") (pintype "passive"))
      (node (ref "J4") (pin "4") (pinfunction "TCT_4") (pintype "passive"))
      (node (ref "J4") (pin "7") (pinfunction "RCT_7") (pintype "passive"))
      (node (ref "R8") (pin "1") (pinfunction "1_1") (pintype "passive"))
    )
    (net (code "46") (name "Net-(J4-YA)") (class "Default")
      (node (ref "J4") (pin "12") (pinfunction "YA_12") (pintype "passive"))
      (node (ref "R32") (pin "2") (pinfunction "2_2") (pintype "passive"))
    )
    (net (code "47") (name "VDDCR") (class "Default")
      (node (ref "C28") (pin "2") (pinfunction "2_2") (pintype "passive"))
      (node (ref "C29") (pin "2") (pinfunction "2_2") (pintype "passive"))
      (node (ref "C31") (pin "2") (pinfunction "2_2") (pintype "passive"))
      (node (ref "C51") (pin "2") (pinfunction "2_2") (pintype "passive"))
      (node (ref "C70") (pin "2") (pinfunction "2_2") (pintype "passive"))
      (node (ref "IC1") (pin "24") (pinfunction "VDDCR_24") (pintype "passive"))
      (node (ref "IC1") (pin "38") (pinfunction "VDDCR_38") (pintype "passive"))
      (node (ref "IC1") (pin "6") (pinfunction "VDDCR_6") (pintype "passive"))
      (node (ref "L2") (pin "1") (pinfunction "1_1") (pintype "passive"))
    )
    (net (code "48") (name "unconnected-(IC1-GPI0{slash}GPO0-Pad36)") (class "Default")
      (node (ref "IC1") (pin "36") (pinfunction "GPI0/GPO0_36") (pintype "passive"))
    )
    (net (code "49") (name "unconnected-(IC1-GPI1{slash}GPO1-Pad39)") (class "Default")
      (node (ref "IC1") (pin "39") (pinfunction "GPI1/GPO1_39") (pintype "passive"))
    )
    (net (code "50") (name "unconnected-(IC1-GPI2{slash}GPO2-Pad40)") (class "Default")
      (node (ref "IC1") (pin "40") (pinfunction "GPI2/GPO2_40") (pintype "passive"))
    )
    (net (code "51") (name "unconnected-(IC1-GPI3{slash}GPO3-Pad49)") (class "Default")
      (node (ref "IC1") (pin "49") (pinfunction "GPI3/GPO3_49") (pintype "passive"))
    )
    (net (code "52") (name "unconnected-(IC1-GPI4{slash}GPO4-Pad23)") (class "Default")
      (node (ref "IC1") (pin "23") (pinfunction "GPI4/GPO4_23") (pintype "passive"))
    )
    (net (code "53") (name "unconnected-(IC1-GPI5{slash}GPO5-Pad22)") (class "Default")
      (node (ref "IC1") (pin "22") (pinfunction "GPI5/GPO5_22") (pintype "passive"))
    )
    (net (code "54") (name "unconnected-(IC1-GPI6{slash}GPO6-Pad21)") (class "Default")
      (node (ref "IC1") (pin "21") (pinfunction "GPI6/GPO6_21") (pintype "passive"))
    )
    (net (code "55") (name "unconnected-(IC1-GPI7{slash}GPO7-Pad16)") (class "Default")
      (node (ref "IC1") (pin "16") (pinfunction "GPI7/GPO7_16") (pintype "passive"))
    )
    (net (code "56") (name "unconnected-(IC1-GPI8{slash}GPO8-Pad15)") (class "Default")
      (node (ref "IC1") (pin "15") (pinfunction "GPI8/GPO8_15") (pintype "passive"))
    )
    (net (code "57") (name "unconnected-(IC1-GPI9{slash}GPO9-Pad33)") (class "Default")
      (node (ref "IC1") (pin "33") (pinfunction "GPI9/GPO9_33") (pintype "passive"))
    )
    (net (code "58") (name "unconnected-(IC1-GPI10{slash}GPO10-Pad29)") (class "Default")
      (node (ref "IC1") (pin "29") (pinfunction "GPI10/GPO10_29") (pintype "passive"))
    )
    (net (code "59") (name "unconnected-(IC1-GPI11{slash}GPO11-Pad26)") (class "Default")
      (node (ref "IC1") (pin "26") (pinfunction "GPI11/GPO11_26") (pintype "passive"))
    )
    (net (code "60") (name "unconnected-(IC1-GPI12{slash}GPO12-Pad27)") (class "Default")
      (node (ref "IC1") (pin "27") (pinfunction "GPI12/GPO12_27") (pintype "passive"))
    )
    (net (code "61") (name "unconnected-(IC1-GPI13{slash}GPO13-Pad28)") (class "Default")
      (node (ref "IC1") (pin "28") (pinfunction "GPI13/GPO13_28") (pintype "passive"))
    )
    (net (code "62") (name "unconnected-(IC1-GPI14{slash}GPO14-Pad30)") (class "Default")
      (node (ref "IC1") (pin "30") (pinfunction "GPI14/GPO14_30") (pintype "passive"))
    )
    (net (code "63") (name "unconnected-(IC1-GPI15{slash}GPO15-Pad31)") (class "Default")
      (node (ref "IC1") (pin "31") (pinfunction "GPI15/GPO15_31") (pintype "passive"))
    )
    (net (code "64") (name "unconnected-(IC1-OSCVDD12-Pad3)") (class "Default")
      (node (ref "IC1") (pin "3") (pinfunction "OSCVDD12_3") (pintype "passive"))
    )
    (net (code "65") (name "unconnected-(IC1-SIO2-Pad12)") (class "Default")
      (node (ref "IC1") (pin "12") (pinfunction "SIO2_12") (pintype "passive"))
    )
    (net (code "66") (name "unconnected-(IC1-SIO3-Pad35)") (class "Default")
      (node (ref "IC1") (pin "35") (pinfunction "SIO3_35") (pintype "passive"))
    )
  )
)
